# DBGadapter.net
KiCad netlist of a schematic drawn in EAGLE
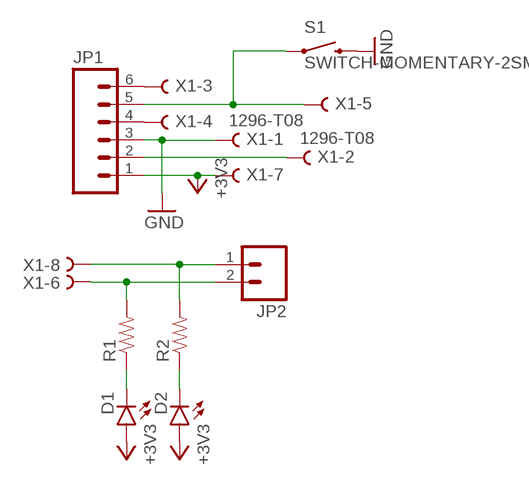
[diagram p0: schematic, sheet 1]

(export (version "E")
  (design (tool "Eeschema 10.0.6"))
  (components
    (comp (ref "D1")
      (value "LED0603")
      (footprint "eagle-import:LED-0603")
      (libsource (lib "eagle-import") (part "LED0603"))
    )
    (comp (ref "D2")
      (value "LED0603")
      (footprint "eagle-import:LED-0603")
      (libsource (lib "eagle-import") (part "LED0603"))
    )
    (comp (ref "JP1")
      (value "M06LOCK_LONGPADS")
      (footprint "eagle-import:1X06_LOCK_LONGPADS")
      (libsource (lib "eagle-import") (part "M06LOCK_LONGPADS"))
    )
    (comp (ref "JP2")
      (value "M02LOCK_LONGPADS")
      (footprint "eagle-import:1X02_LOCK_LONGPADS")
      (libsource (lib "eagle-import") (part "M02LOCK_LONGPADS"))
    )
    (comp (ref "R1")
      (value "RESISTOR0805-RES")
      (footprint "eagle-import:0805")
      (libsource (lib "eagle-import") (part "RESISTOR0805-RES"))
    )
    (comp (ref "R2")
      (value "RESISTOR0805-RES")
      (footprint "eagle-import:0805")
      (libsource (lib "eagle-import") (part "RESISTOR0805-RES"))
    )
    (comp (ref "S1")
      (value "SWITCH-MOMENTARY-2SMD")
      (footprint "eagle-import:TACTILE-SWITCH-SMD")
      (libsource (lib "eagle-import") (part "SWITCH-MOMENTARY-2SMD"))
    )
    (comp (ref "X1")
      (value "1296-T08")
      (footprint "eagle-import:1296-08")
      (libsource (lib "eagle-import") (part "1296-T08"))
    )
  )
  (nets
    (net (code "1") (name "+3V3") (class "Default")
      (node (ref "D1") (pin "A") (pinfunction "A_A") (pintype "passive"))
      (node (ref "D2") (pin "A") (pinfunction "A_A") (pintype "passive"))
      (node (ref "JP1") (pin "1") (pinfunction "1_1") (pintype "passive"))
      (node (ref "X1") (pin "7") (pinfunction "B_7") (pintype "passive"))
    )
    (net (code "2") (name "GND") (class "Default")
      (node (ref "JP1") (pin "3") (pinfunction "3_3") (pintype "passive"))
      (node (ref "S1") (pin "3") (pinfunction "2_3") (pintype "passive"))
      (node (ref "X1") (pin "1") (pinfunction "B_1") (pintype "passive"))
    )
    (net (code "3") (name "Net-(D1-PadC)") (class "Default")
      (node (ref "D1") (pin "C") (pinfunction "C_C") (pintype "passive"))
      (node (ref "R1") (pin "1") (pinfunction "1_1") (pintype "passive"))
    )
    (net (code "4") (name "Net-(D2-PadC)") (class "Default")
      (node (ref "D2") (pin "C") (pinfunction "C_C") (pintype "passive"))
      (node (ref "R2") (pin "1") (pinfunction "1_1") (pintype "passive"))
    )
    (net (code "5") (name "Net-(X1B-B)") (class "Default")
      (node (ref "JP1") (pin "2") (pinfunction "2_2") (pintype "passive"))
      (node (ref "X1") (pin "2") (pinfunction "B_2") (pintype "passive"))
    )
    (net (code "6") (name "Net-(X1C-B)") (class "Default")
      (node (ref "JP1") (pin "6") (pinfunction "6_6") (pintype "passive"))
      (node (ref "X1") (pin "3") (pinfunction "B_3") (pintype "passive"))
    )
    (net (code "7") (name "Net-(X1D-B)") (class "Default")
      (node (ref "JP1") (pin "4") (pinfunction "4_4") (pintype "passive"))
      (node (ref "X1") (pin "4") (pinfunction "B_4") (pintype "passive"))
    )
    (net (code "8") (name "Net-(X1E-B)") (class "Default")
      (node (ref "JP1") (pin "5") (pinfunction "5_5") (pintype "passive"))
      (node (ref "S1") (pin "1") (pinfunction "1_1") (pintype "passive"))
      (node (ref "X1") (pin "5") (pinfunction "B_5") (pintype "passive"))
    )
    (net (code "9") (name "Net-(X1F-B)") (class "Default")
      (node (ref "JP2") (pin "2") (pinfunction "2_2") (pintype "passive"))
      (node (ref "R1") (pin "2") (pinfunction "2_2") (pintype "passive"))
      (node (ref "X1") (pin "6") (pinfunction "B_6") (pintype "passive"))
    )
    (net (code "10") (name "Net-(X1H-B)") (class "Default")
      (node (ref "JP2") (pin "1") (pinfunction "1_1") (pintype "passive"))
      (node (ref "R2") (pin "2") (pinfunction "2_2") (pintype "passive"))
      (node (ref "X1") (pin "8") (pinfunction "B_8") (pintype "passive"))
    )
  )
)
